# evaluation.net
KiCad netlist of a schematic drawn in EAGLE
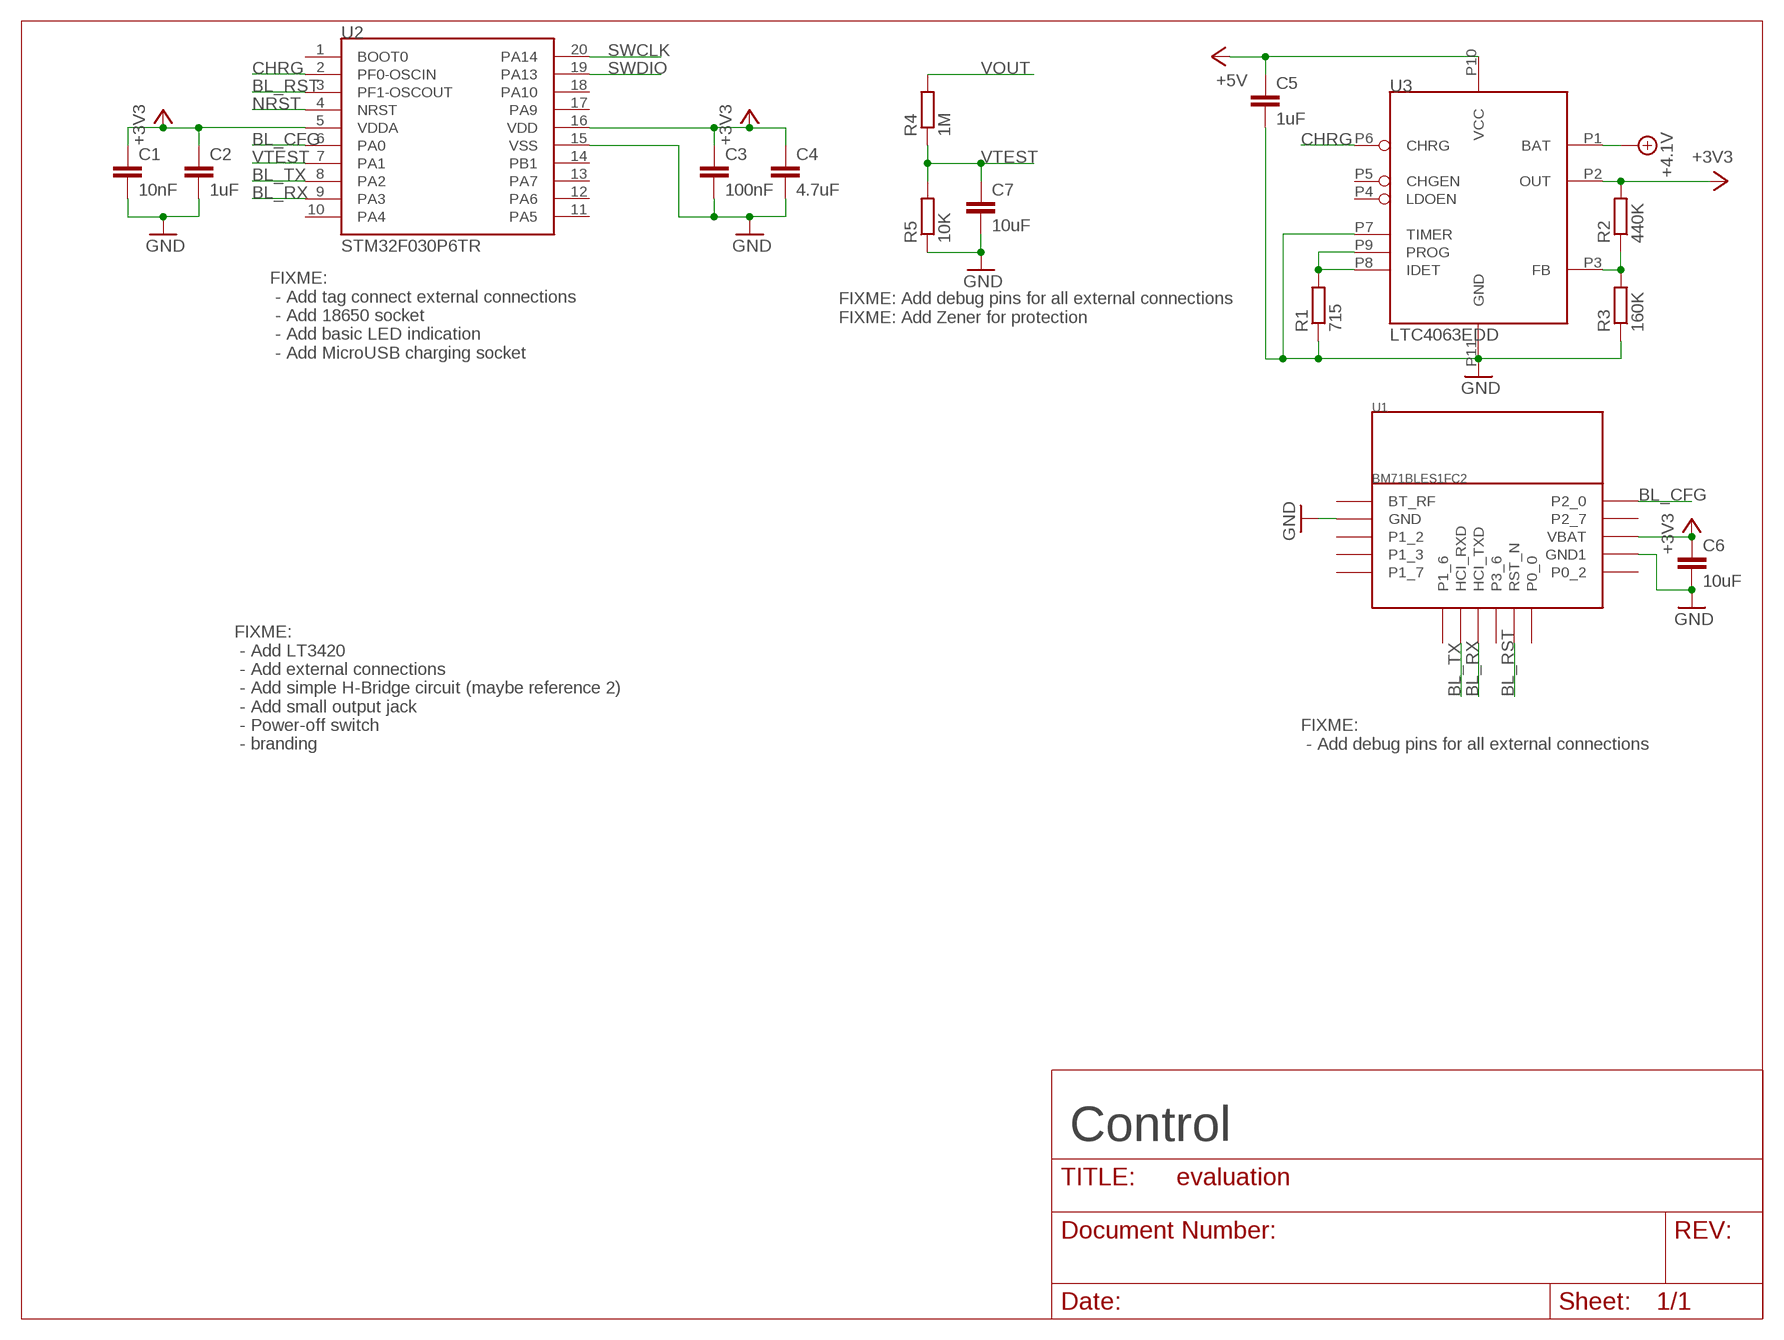
[diagram p0: schematic, sheet 1]

(export (version "E")
  (design (tool "Eeschema 10.0.6"))
  (components
    (comp (ref "C1")
      (value "10nF")
      (footprint "eagle-import:C0402")
      (libsource (lib "eagle-import") (part "C-0402"))
    )
    (comp (ref "C2")
      (value "1uF")
      (footprint "eagle-import:C0402")
      (libsource (lib "eagle-import") (part "C-0402"))
    )
    (comp (ref "C3")
      (value "100nF")
      (footprint "eagle-import:C0402")
      (libsource (lib "eagle-import") (part "C-0402"))
    )
    (comp (ref "C4")
      (value "4.7uF")
      (footprint "eagle-import:C0402")
      (libsource (lib "eagle-import") (part "C-0402"))
    )
    (comp (ref "C5")
      (value "1uF")
      (footprint "eagle-import:C0402")
      (libsource (lib "eagle-import") (part "C-0402"))
    )
    (comp (ref "C6")
      (value "10uF")
      (footprint "eagle-import:C0402")
      (libsource (lib "eagle-import") (part "C-0402"))
    )
    (comp (ref "C7")
      (value "10uF")
      (footprint "eagle-import:C0402")
      (libsource (lib "eagle-import") (part "C-0402"))
    )
    (comp (ref "R1")
      (value "715")
      (footprint "eagle-import:R0402")
      (libsource (lib "eagle-import") (part "R-0402"))
    )
    (comp (ref "R2")
      (value "440K")
      (footprint "eagle-import:R0402")
      (libsource (lib "eagle-import") (part "R-0402"))
    )
    (comp (ref "R3")
      (value "160K")
      (footprint "eagle-import:R0402")
      (libsource (lib "eagle-import") (part "R-0402"))
    )
    (comp (ref "R4")
      (value "1M")
      (footprint "eagle-import:R0805")
      (libsource (lib "eagle-import") (part "R-0805"))
    )
    (comp (ref "R5")
      (value "10K")
      (footprint "eagle-import:R0805")
      (libsource (lib "eagle-import") (part "R-0805"))
    )
    (comp (ref "U1")
      (value "BM71BLES1FC2")
      (footprint "eagle-import:BM71BLES1FC2")
      (libsource (lib "eagle-import") (part "BM71BLES1FC2"))
    )
    (comp (ref "U2")
      (value "STM32F030P6TR")
      (footprint "eagle-import:TSSOP20")
      (libsource (lib "eagle-import") (part "STM32F030P6TR"))
    )
    (comp (ref "U3")
      (value "LTC4063EDD")
      (footprint "eagle-import:LTC4063")
      (libsource (lib "eagle-import") (part "LTC4063EDD"))
    )
  )
  (nets
    (net (code "1") (name "+3V3") (class "Default")
      (node (ref "C1") (pin "1") (pinfunction "1_1") (pintype "passive"))
      (node (ref "C2") (pin "1") (pinfunction "1_1") (pintype "passive"))
      (node (ref "C3") (pin "1") (pinfunction "1_1") (pintype "passive"))
      (node (ref "C4") (pin "1") (pinfunction "1_1") (pintype "passive"))
      (node (ref "C6") (pin "1") (pinfunction "1_1") (pintype "passive"))
      (node (ref "R2") (pin "2") (pinfunction "2_2") (pintype "passive"))
      (node (ref "U1") (pin "P$14") (pinfunction "VBAT_P$14") (pintype "bidirectional"))
      (node (ref "U2") (pin "16") (pinfunction "VDD_16") (pintype "bidirectional"))
      (node (ref "U2") (pin "5") (pinfunction "VDDA_5") (pintype "bidirectional"))
      (node (ref "U3") (pin "P2") (pinfunction "OUT_P2") (pintype "output"))
    )
    (net (code "2") (name "+4.1V") (class "Default")
      (node (ref "U3") (pin "P1") (pinfunction "BAT_P1") (pintype "output"))
    )
    (net (code "3") (name "+5V") (class "Default")
      (node (ref "C5") (pin "1") (pinfunction "1_1") (pintype "passive"))
      (node (ref "U3") (pin "P10") (pinfunction "VCC_P10") (pintype "power_in"))
    )
    (net (code "4") (name "/BL_CFG") (class "Default")
      (node (ref "U1") (pin "P$16") (pinfunction "P2_0_P$16") (pintype "bidirectional"))
      (node (ref "U2") (pin "6") (pinfunction "PA0_6") (pintype "bidirectional"))
    )
    (net (code "5") (name "/BL_RST") (class "Default")
      (node (ref "U1") (pin "P$10") (pinfunction "RST_N_P$10") (pintype "bidirectional"))
      (node (ref "U2") (pin "3") (pinfunction "PF1-OSCOUT_3") (pintype "bidirectional"))
    )
    (net (code "6") (name "/BL_RX") (class "Default")
      (node (ref "U1") (pin "P$8") (pinfunction "HCI_TXD_P$8") (pintype "bidirectional"))
      (node (ref "U2") (pin "9") (pinfunction "PA3_9") (pintype "bidirectional"))
    )
    (net (code "7") (name "/BL_TX") (class "Default")
      (node (ref "U1") (pin "P$7") (pinfunction "HCI_RXD_P$7") (pintype "bidirectional"))
      (node (ref "U2") (pin "8") (pinfunction "PA2_8") (pintype "bidirectional"))
    )
    (net (code "8") (name "/CHRG") (class "Default")
      (node (ref "U2") (pin "2") (pinfunction "PF0-OSCIN_2") (pintype "bidirectional"))
      (node (ref "U3") (pin "P6") (pinfunction "CHRG_P6") (pintype "output"))
    )
    (net (code "9") (name "/NRST") (class "Default")
      (node (ref "U2") (pin "4") (pinfunction "NRST_4") (pintype "bidirectional"))
    )
    (net (code "10") (name "/SWCLK") (class "Default")
      (node (ref "U2") (pin "20") (pinfunction "PA14_20") (pintype "bidirectional"))
    )
    (net (code "11") (name "/SWDIO") (class "Default")
      (node (ref "U2") (pin "19") (pinfunction "PA13_19") (pintype "bidirectional"))
    )
    (net (code "12") (name "/VOUT") (class "Default")
      (node (ref "R4") (pin "2") (pinfunction "2_2") (pintype "passive"))
    )
    (net (code "13") (name "/VTEST") (class "Default")
      (node (ref "C7") (pin "1") (pinfunction "1_1") (pintype "passive"))
      (node (ref "R4") (pin "1") (pinfunction "1_1") (pintype "passive"))
      (node (ref "R5") (pin "2") (pinfunction "2_2") (pintype "passive"))
      (node (ref "U2") (pin "7") (pinfunction "PA1_7") (pintype "bidirectional"))
    )
    (net (code "14") (name "GND") (class "Default")
      (node (ref "C1") (pin "2") (pinfunction "2_2") (pintype "passive"))
      (node (ref "C2") (pin "2") (pinfunction "2_2") (pintype "passive"))
      (node (ref "C3") (pin "2") (pinfunction "2_2") (pintype "passive"))
      (node (ref "C4") (pin "2") (pinfunction "2_2") (pintype "passive"))
      (node (ref "C5") (pin "2") (pinfunction "2_2") (pintype "passive"))
      (node (ref "C6") (pin "2") (pinfunction "2_2") (pintype "passive"))
      (node (ref "C7") (pin "2") (pinfunction "2_2") (pintype "passive"))
      (node (ref "R1") (pin "1") (pinfunction "1_1") (pintype "passive"))
      (node (ref "R3") (pin "1") (pinfunction "1_1") (pintype "passive"))
      (node (ref "R5") (pin "1") (pinfunction "1_1") (pintype "passive"))
      (node (ref "U1") (pin "P$13") (pinfunction "GND1_P$13") (pintype "bidirectional"))
      (node (ref "U1") (pin "P$2") (pinfunction "GND_P$2") (pintype "bidirectional"))
      (node (ref "U2") (pin "15") (pinfunction "VSS_15") (pintype "bidirectional"))
      (node (ref "U3") (pin "P11") (pinfunction "GND_P11") (pintype "power_in"))
      (node (ref "U3") (pin "P7") (pinfunction "TIMER_P7") (pintype "passive"))
    )
    (net (code "15") (name "Net-(U3-FB)") (class "Default")
      (node (ref "R2") (pin "1") (pinfunction "1_1") (pintype "passive"))
      (node (ref "R3") (pin "2") (pinfunction "2_2") (pintype "passive"))
      (node (ref "U3") (pin "P3") (pinfunction "FB_P3") (pintype "passive"))
    )
    (net (code "16") (name "Net-(U3-IDET)") (class "Default")
      (node (ref "R1") (pin "2") (pinfunction "2_2") (pintype "passive"))
      (node (ref "U3") (pin "P8") (pinfunction "IDET_P8") (pintype "passive"))
      (node (ref "U3") (pin "P9") (pinfunction "PROG_P9") (pintype "passive"))
    )
    (net (code "17") (name "unconnected-(U1-BT_RF-PadP$1)") (class "Default")
      (node (ref "U1") (pin "P$1") (pinfunction "BT_RF_P$1") (pintype "bidirectional"))
    )
    (net (code "18") (name "unconnected-(U1-P0_0-PadP$11)") (class "Default")
      (node (ref "U1") (pin "P$11") (pinfunction "P0_0_P$11") (pintype "bidirectional"))
    )
    (net (code "19") (name "unconnected-(U1-P0_2-PadP$12)") (class "Default")
      (node (ref "U1") (pin "P$12") (pinfunction "P0_2_P$12") (pintype "bidirectional"))
    )
    (net (code "20") (name "unconnected-(U1-P1_2-PadP$3)") (class "Default")
      (node (ref "U1") (pin "P$3") (pinfunction "P1_2_P$3") (pintype "bidirectional"))
    )
    (net (code "21") (name "unconnected-(U1-P1_3-PadP$4)") (class "Default")
      (node (ref "U1") (pin "P$4") (pinfunction "P1_3_P$4") (pintype "bidirectional"))
    )
    (net (code "22") (name "unconnected-(U1-P1_6-PadP$6)") (class "Default")
      (node (ref "U1") (pin "P$6") (pinfunction "P1_6_P$6") (pintype "bidirectional"))
    )
    (net (code "23") (name "unconnected-(U1-P1_7-PadP$5)") (class "Default")
      (node (ref "U1") (pin "P$5") (pinfunction "P1_7_P$5") (pintype "bidirectional"))
    )
    (net (code "24") (name "unconnected-(U1-P2_7-PadP$15)") (class "Default")
      (node (ref "U1") (pin "P$15") (pinfunction "P2_7_P$15") (pintype "bidirectional"))
    )
    (net (code "25") (name "unconnected-(U1-P3_6-PadP$9)") (class "Default")
      (node (ref "U1") (pin "P$9") (pinfunction "P3_6_P$9") (pintype "bidirectional"))
    )
    (net (code "26") (name "unconnected-(U2-BOOT0-Pad1)") (class "Default")
      (node (ref "U2") (pin "1") (pinfunction "BOOT0_1") (pintype "bidirectional"))
    )
    (net (code "27") (name "unconnected-(U2-PA4-Pad10)") (class "Default")
      (node (ref "U2") (pin "10") (pinfunction "PA4_10") (pintype "bidirectional"))
    )
    (net (code "28") (name "unconnected-(U2-PA5-Pad11)") (class "Default")
      (node (ref "U2") (pin "11") (pinfunction "PA5_11") (pintype "bidirectional"))
    )
    (net (code "29") (name "unconnected-(U2-PA6-Pad12)") (class "Default")
      (node (ref "U2") (pin "12") (pinfunction "PA6_12") (pintype "bidirectional"))
    )
    (net (code "30") (name "unconnected-(U2-PA7-Pad13)") (class "Default")
      (node (ref "U2") (pin "13") (pinfunction "PA7_13") (pintype "bidirectional"))
    )
    (net (code "31") (name "unconnected-(U2-PA9-Pad17)") (class "Default")
      (node (ref "U2") (pin "17") (pinfunction "PA9_17") (pintype "bidirectional"))
    )
    (net (code "32") (name "unconnected-(U2-PA10-Pad18)") (class "Default")
      (node (ref "U2") (pin "18") (pinfunction "PA10_18") (pintype "bidirectional"))
    )
    (net (code "33") (name "unconnected-(U2-PB1-Pad14)") (class "Default")
      (node (ref "U2") (pin "14") (pinfunction "PB1_14") (pintype "bidirectional"))
    )
    (net (code "34") (name "unconnected-(U3-CHGEN-PadP5)") (class "Default")
      (node (ref "U3") (pin "P5") (pinfunction "CHGEN_P5") (pintype "input"))
    )
    (net (code "35") (name "unconnected-(U3-LDOEN-PadP4)") (class "Default")
      (node (ref "U3") (pin "P4") (pinfunction "LDOEN_P4") (pintype "input"))
    )
  )
)
